# design1.net
KiCad netlist of a schematic drawn in EAGLE
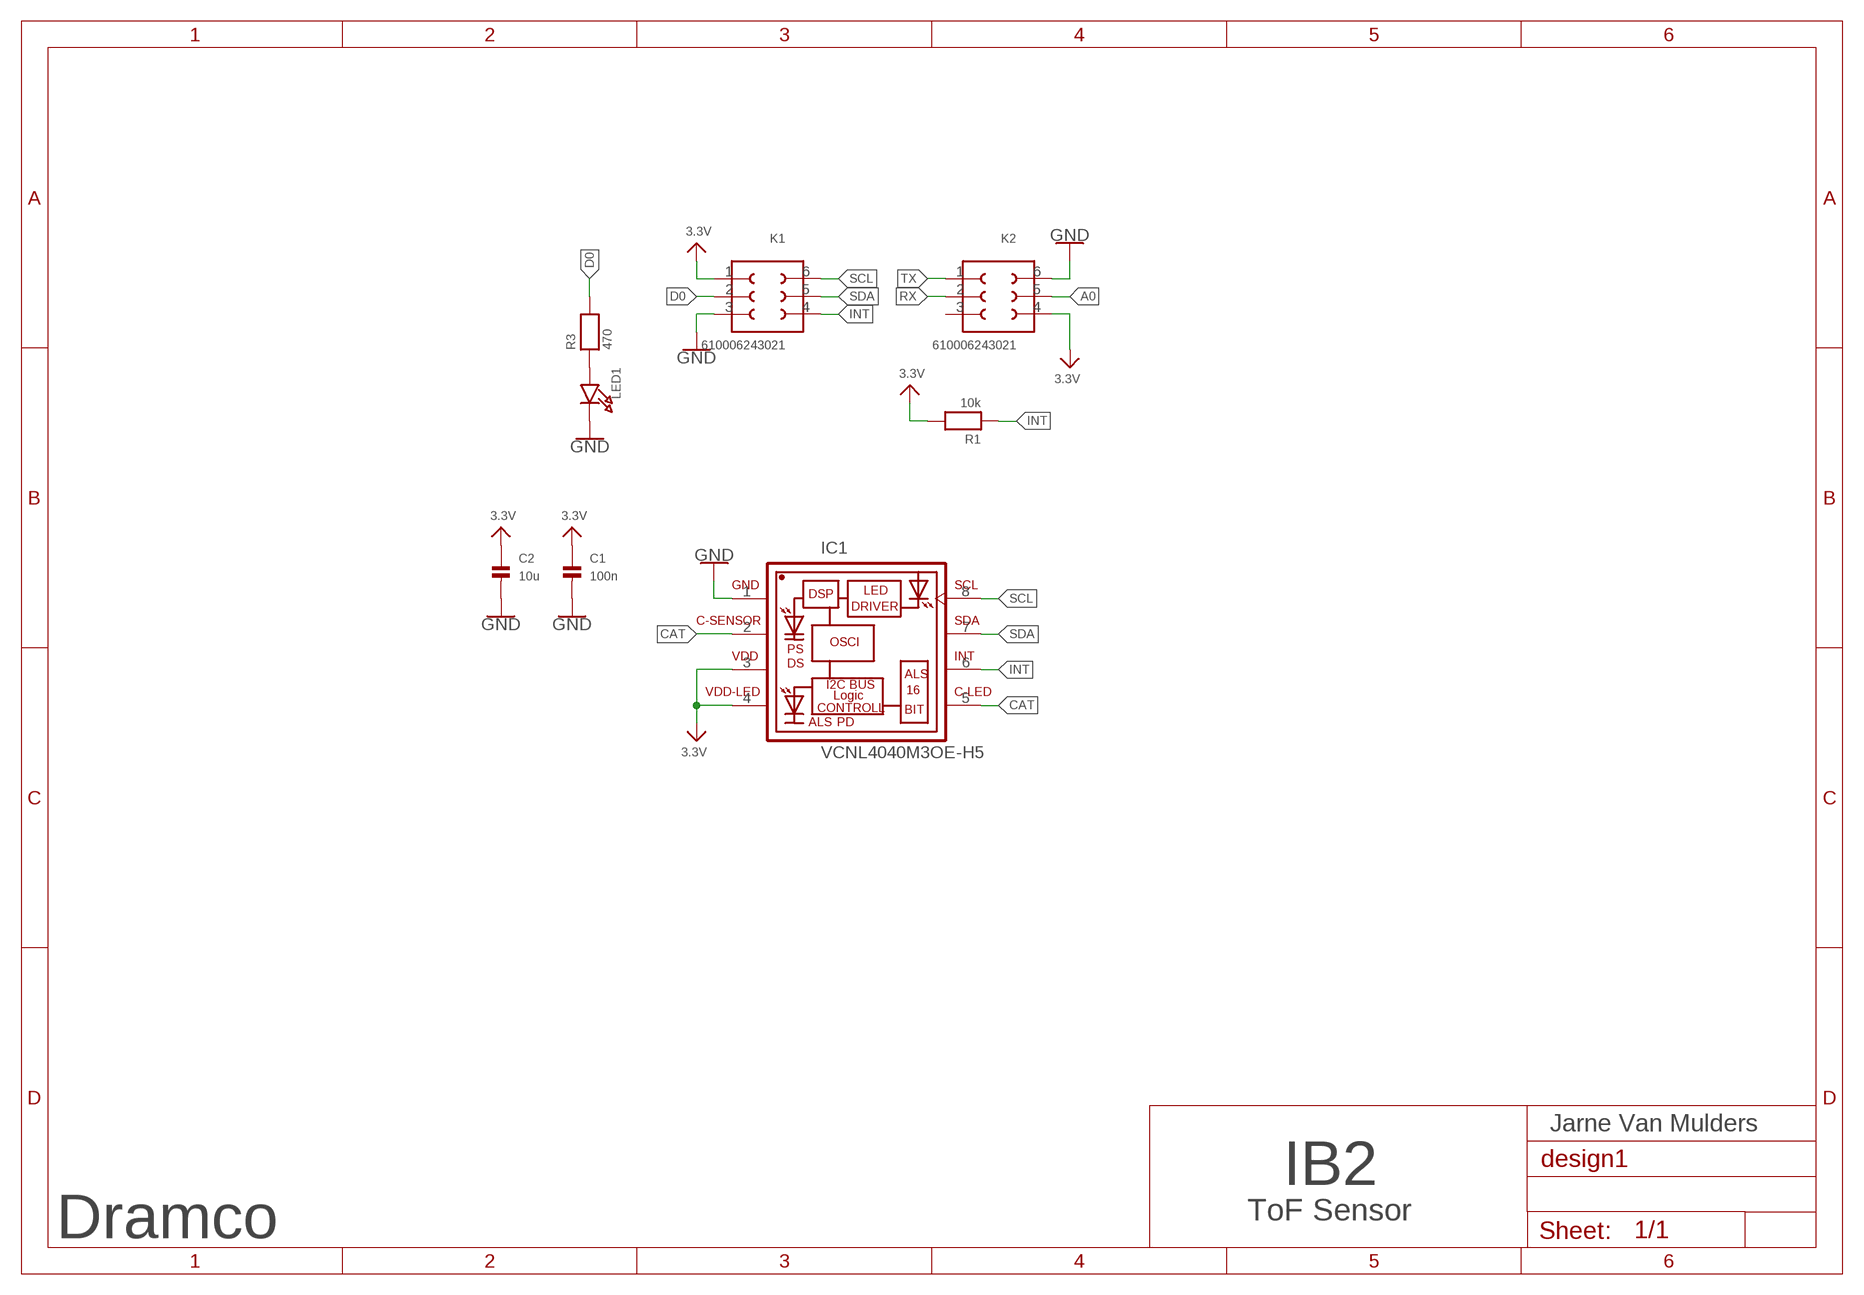
[diagram p0: schematic, sheet 1]

(export (version "E")
  (design (tool "Eeschema 10.0.6"))
  (components
    (comp (ref "C1")
      (value "100n")
      (footprint "eagle-import:0603")
      (libsource (lib "eagle-import") (part "CAP_CERAMIC0603"))
    )
    (comp (ref "C2")
      (value "10u")
      (footprint "eagle-import:0805")
      (libsource (lib "eagle-import") (part "CAP_CERAMIC0805"))
    )
    (comp (ref "IC1")
      (value "VCNL4040M3OE-H5")
      (footprint "eagle-import:VISHAY_VCNL4040_4.34X2.35X3.65")
      (fields (field (name "MF") "Vishay Semiconductor"))
      (libsource (lib "eagle-import") (part "VCNL4040M3OE-H5"))
    )
    (comp (ref "K1")
      (value "610006243021")
      (footprint "eagle-import:610006243021")
      (libsource (lib "eagle-import") (part "610006243021"))
    )
    (comp (ref "K2")
      (value "610006243021")
      (footprint "eagle-import:610006243021")
      (libsource (lib "eagle-import") (part "610006243021"))
    )
    (comp (ref "LED1")
      (value "LED0805")
      (footprint "eagle-import:CHIPLED_0805")
      (libsource (lib "eagle-import") (part "LED0805"))
    )
    (comp (ref "R1")
      (value "10k")
      (footprint "eagle-import:0603")
      (libsource (lib "eagle-import") (part "RESISTOR0603"))
    )
    (comp (ref "R3")
      (value "470")
      (footprint "eagle-import:0603")
      (libsource (lib "eagle-import") (part "RESISTOR0603"))
    )
  )
  (nets
    (net (code "1") (name "3.3V") (class "Default")
      (node (ref "C1") (pin "1") (pinfunction "P$1_1") (pintype "passive"))
      (node (ref "C2") (pin "1") (pinfunction "P$1_1") (pintype "passive"))
      (node (ref "IC1") (pin "3") (pinfunction "VDD_3") (pintype "power_in"))
      (node (ref "IC1") (pin "4") (pinfunction "VDD-LED_4") (pintype "power_in"))
      (node (ref "K1") (pin "1") (pinfunction "1_1") (pintype "passive"))
      (node (ref "K2") (pin "4") (pinfunction "4_4") (pintype "passive"))
      (node (ref "R1") (pin "2") (pinfunction "2_2") (pintype "passive"))
    )
    (net (code "2") (name "A0") (class "Default")
      (node (ref "K2") (pin "5") (pinfunction "5_5") (pintype "passive"))
    )
    (net (code "3") (name "CAT") (class "Default")
      (node (ref "IC1") (pin "2") (pinfunction "C-SENSOR_2") (pintype "output"))
      (node (ref "IC1") (pin "5") (pinfunction "C-LED_5") (pintype "output"))
    )
    (net (code "4") (name "D0") (class "Default")
      (node (ref "K1") (pin "2") (pinfunction "2_2") (pintype "passive"))
      (node (ref "R3") (pin "2") (pinfunction "2_2") (pintype "passive"))
    )
    (net (code "5") (name "GND") (class "Default")
      (node (ref "C1") (pin "2") (pinfunction "P$2_2") (pintype "passive"))
      (node (ref "C2") (pin "2") (pinfunction "P$2_2") (pintype "passive"))
      (node (ref "IC1") (pin "1") (pinfunction "GND_1") (pintype "power_in"))
      (node (ref "K1") (pin "3") (pinfunction "3_3") (pintype "passive"))
      (node (ref "K2") (pin "6") (pinfunction "6_6") (pintype "passive"))
      (node (ref "LED1") (pin "C") (pinfunction "C_C") (pintype "passive"))
    )
    (net (code "6") (name "INT") (class "Default")
      (node (ref "IC1") (pin "6") (pinfunction "INT_6") (pintype "output"))
      (node (ref "K1") (pin "4") (pinfunction "4_4") (pintype "passive"))
      (node (ref "R1") (pin "1") (pinfunction "1_1") (pintype "passive"))
    )
    (net (code "7") (name "Net-(LED1-PadA)") (class "Default")
      (node (ref "LED1") (pin "A") (pinfunction "A_A") (pintype "passive"))
      (node (ref "R3") (pin "1") (pinfunction "1_1") (pintype "passive"))
    )
    (net (code "8") (name "RX") (class "Default")
      (node (ref "K2") (pin "2") (pinfunction "2_2") (pintype "passive"))
    )
    (net (code "9") (name "SCL") (class "Default")
      (node (ref "IC1") (pin "8") (pinfunction "SCL_8") (pintype "input"))
      (node (ref "K1") (pin "6") (pinfunction "6_6") (pintype "passive"))
    )
    (net (code "10") (name "SDA") (class "Default")
      (node (ref "IC1") (pin "7") (pinfunction "SDA_7") (pintype "bidirectional"))
      (node (ref "K1") (pin "5") (pinfunction "5_5") (pintype "passive"))
    )
    (net (code "11") (name "TX") (class "Default")
      (node (ref "K2") (pin "1") (pinfunction "1_1") (pintype "passive"))
    )
    (net (code "12") (name "unconnected-(K2-Pad3)") (class "Default")
      (node (ref "K2") (pin "3") (pinfunction "3_3") (pintype "passive"))
    )
  )
)
